# Schematic.net
KiCad netlist of a schematic drawn in EAGLE
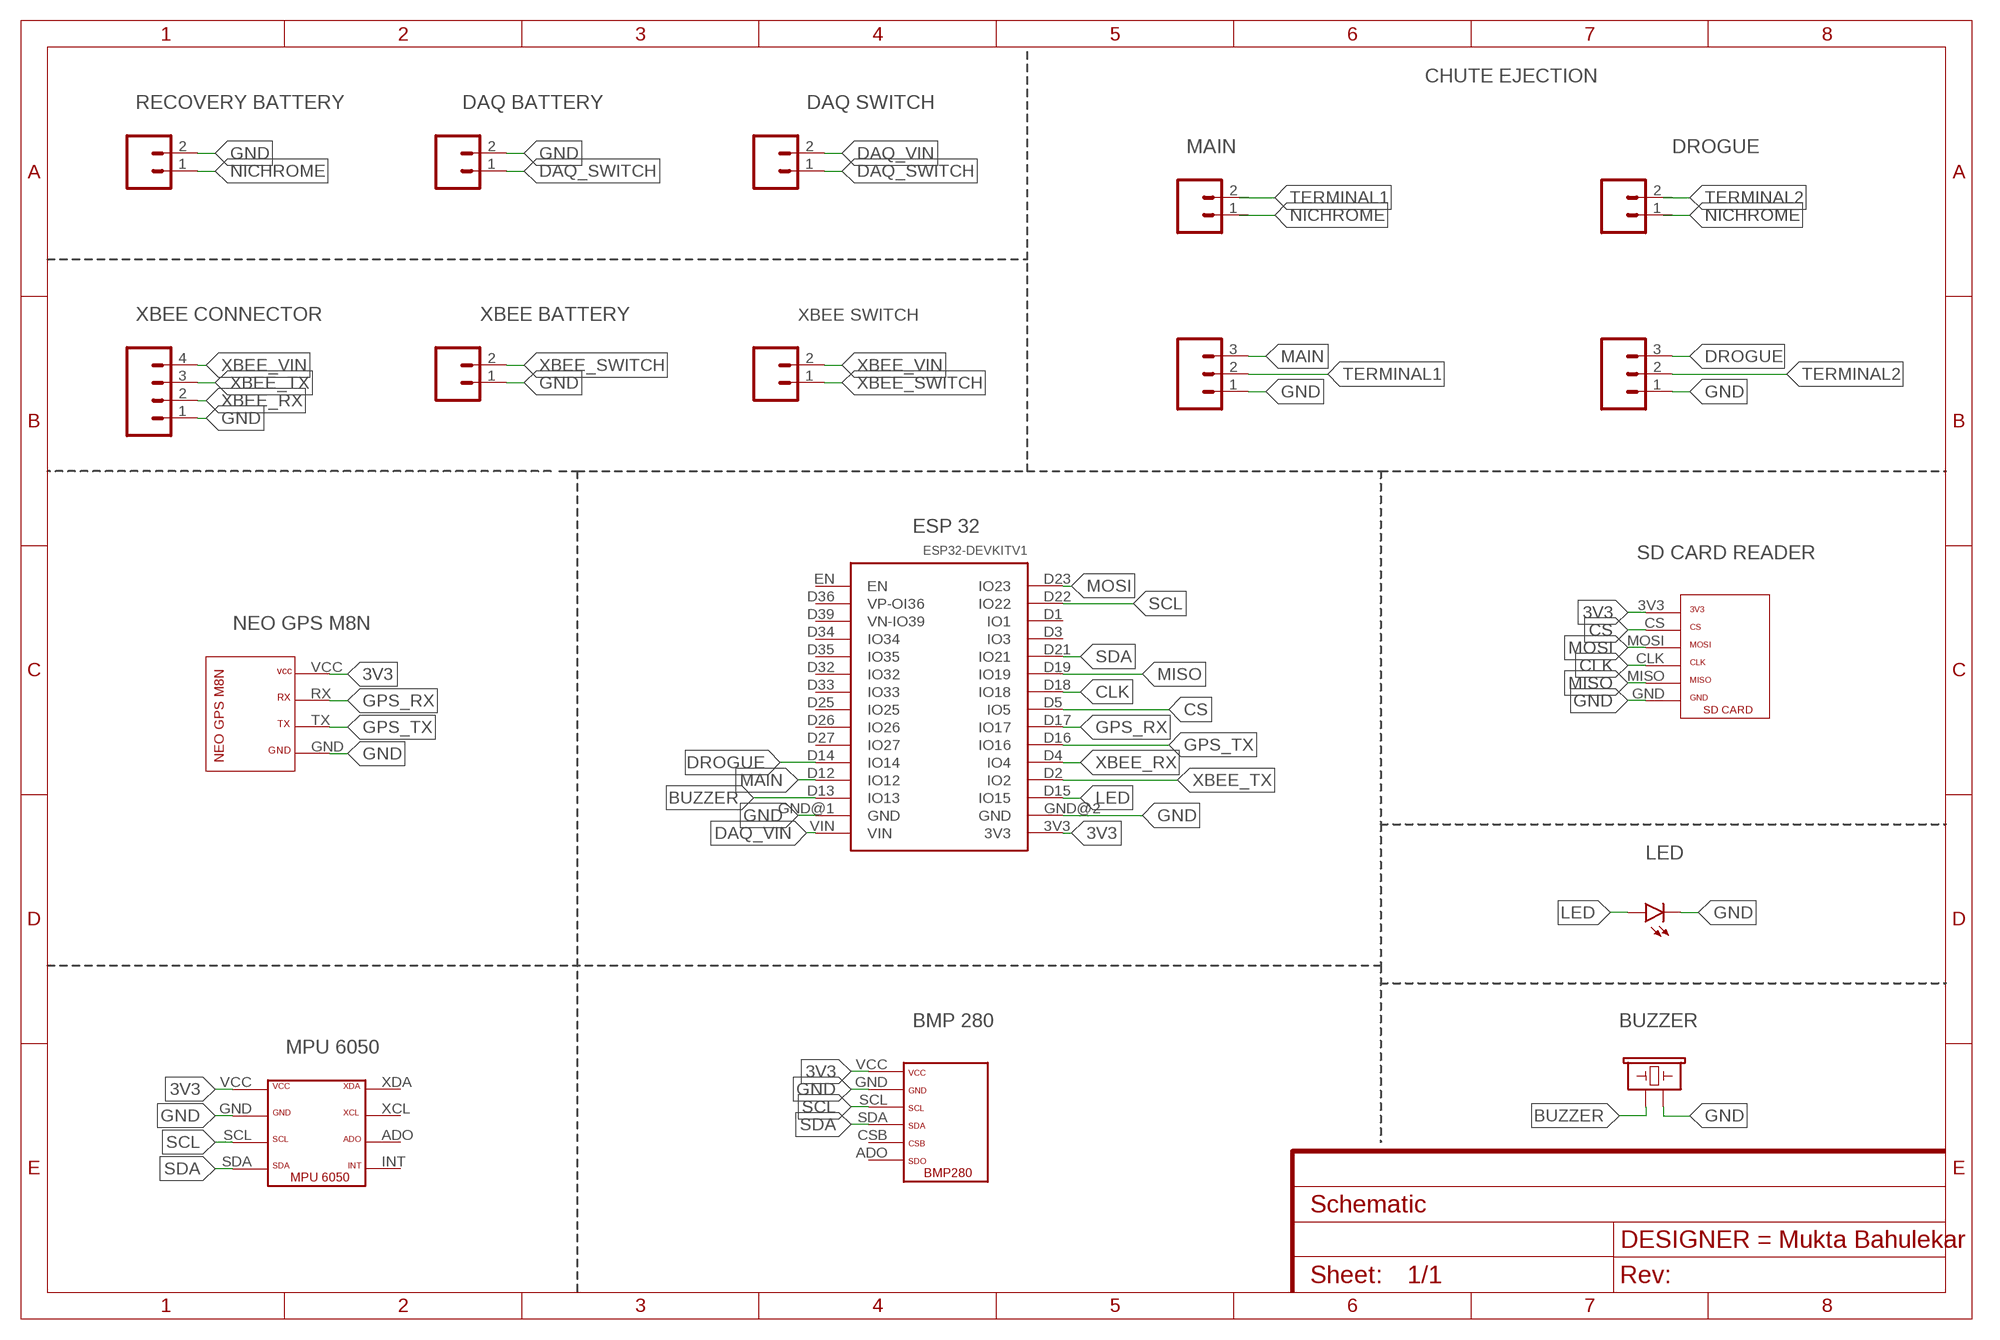
[diagram p0: schematic, sheet 1]

(export (version "E")
  (design (tool "Eeschema 10.0.6"))
  (components
    (comp (ref "J1")
      (value "455-1750-1-ND")
      (footprint "eagle-import:1X03")
      (libsource (lib "eagle-import") (part "CONN_03"))
    )
    (comp (ref "J2")
      (value "455-1750-1-ND")
      (footprint "eagle-import:1X03")
      (libsource (lib "eagle-import") (part "CONN_03"))
    )
    (comp (ref "J8")
      (value "CONN_02PTH4")
      (footprint "eagle-import:1X02_XTRA_BIG")
      (libsource (lib "eagle-import") (part "CONN_02PTH4"))
    )
    (comp (ref "J11")
      (value "CONN_04PTH")
      (footprint "eagle-import:1X04")
      (libsource (lib "eagle-import") (part "CONN_04PTH"))
    )
    (comp (ref "J12")
      (value "CONN_02PTH4")
      (footprint "eagle-import:1X02_XTRA_BIG")
      (libsource (lib "eagle-import") (part "CONN_02PTH4"))
    )
    (comp (ref "J13")
      (value "CONN_02PTH4")
      (footprint "eagle-import:1X02_XTRA_BIG")
      (libsource (lib "eagle-import") (part "CONN_02PTH4"))
    )
    (comp (ref "J14")
      (value "CONN_02PTH4")
      (footprint "eagle-import:1X02_XTRA_BIG")
      (libsource (lib "eagle-import") (part "CONN_02PTH4"))
    )
    (comp (ref "J15")
      (value "CONN_02PTH4")
      (footprint "eagle-import:1X02_XTRA_BIG")
      (libsource (lib "eagle-import") (part "CONN_02PTH4"))
    )
    (comp (ref "J16")
      (value "CONN_02PTH4")
      (footprint "eagle-import:1X02_XTRA_BIG")
      (libsource (lib "eagle-import") (part "CONN_02PTH4"))
    )
    (comp (ref "J17")
      (value "CONN_02PTH4")
      (footprint "eagle-import:1X02_XTRA_BIG")
      (libsource (lib "eagle-import") (part "CONN_02PTH4"))
    )
    (comp (ref "LED1")
      (value "LED5MM")
      (footprint "eagle-import:LED5MM")
      (libsource (lib "eagle-import") (part "LED5MM"))
    )
    (comp (ref "LS1")
      (value "BUZZER-PTH")
      (footprint "eagle-import:BUZZER-12MM")
      (libsource (lib "eagle-import") (part "BUZZER-PTH"))
    )
    (comp (ref "U$1")
      (value "ESP32DEVKITV1")
      (footprint "eagle-import:ESP32-DEVKITV1")
      (libsource (lib "eagle-import") (part "ESP32DEVKITV1"))
    )
    (comp (ref "U$2")
      (value "BMP280")
      (footprint "eagle-import:BMP280")
      (libsource (lib "eagle-import") (part "BMP280"))
    )
    (comp (ref "U$3")
      (value "MINISD")
      (footprint "eagle-import:MINISD")
      (libsource (lib "eagle-import") (part "MINISD"))
    )
    (comp (ref "U$4")
      (value "MPU6050")
      (footprint "eagle-import:MPU6050")
      (libsource (lib "eagle-import") (part "MPU6050"))
    )
    (comp (ref "U$5")
      (value "NEOM8N")
      (footprint "eagle-import:NEOM8M")
      (libsource (lib "eagle-import") (part "NEOM8N"))
    )
  )
  (nets
    (net (code "1") (name "3V3") (class "Default")
      (node (ref "U$1") (pin "3V3") (pinfunction "3V3_3V3") (pintype "bidirectional"))
      (node (ref "U$2") (pin "VCC") (pinfunction "VCC_VCC") (pintype "bidirectional"))
      (node (ref "U$3") (pin "3V3") (pinfunction "3V3_3V3") (pintype "bidirectional"))
      (node (ref "U$4") (pin "VCC") (pinfunction "VCC_VCC") (pintype "bidirectional"))
      (node (ref "U$5") (pin "VCC") (pinfunction "VCC_VCC") (pintype "bidirectional"))
    )
    (net (code "2") (name "BUZZER") (class "Default")
      (node (ref "LS1") (pin "+") (pinfunction "1_+") (pintype "passive"))
      (node (ref "U$1") (pin "D13") (pinfunction "IO13_D13") (pintype "bidirectional"))
    )
    (net (code "3") (name "CLK") (class "Default")
      (node (ref "U$1") (pin "D18") (pinfunction "IO18_D18") (pintype "bidirectional"))
      (node (ref "U$3") (pin "CLK") (pinfunction "CLK_CLK") (pintype "bidirectional"))
    )
    (net (code "4") (name "CS") (class "Default")
      (node (ref "U$1") (pin "D5") (pinfunction "IO5_D5") (pintype "bidirectional"))
      (node (ref "U$3") (pin "CS") (pinfunction "CS_CS") (pintype "bidirectional"))
    )
    (net (code "5") (name "DAQ_SWITCH") (class "Default")
      (node (ref "J12") (pin "1") (pinfunction "1_1") (pintype "passive"))
      (node (ref "J13") (pin "1") (pinfunction "1_1") (pintype "passive"))
    )
    (net (code "6") (name "DAQ_VIN") (class "Default")
      (node (ref "J13") (pin "2") (pinfunction "2_2") (pintype "passive"))
      (node (ref "U$1") (pin "VIN") (pinfunction "VIN_VIN") (pintype "bidirectional"))
    )
    (net (code "7") (name "DROGUE") (class "Default")
      (node (ref "J1") (pin "3") (pinfunction "3_3") (pintype "passive"))
      (node (ref "U$1") (pin "D14") (pinfunction "IO14_D14") (pintype "bidirectional"))
    )
    (net (code "8") (name "GND") (class "Default")
      (node (ref "J1") (pin "1") (pinfunction "1_1") (pintype "passive"))
      (node (ref "J11") (pin "1") (pinfunction "1_1") (pintype "passive"))
      (node (ref "J12") (pin "2") (pinfunction "2_2") (pintype "passive"))
      (node (ref "J15") (pin "1") (pinfunction "1_1") (pintype "passive"))
      (node (ref "J2") (pin "1") (pinfunction "1_1") (pintype "passive"))
      (node (ref "J8") (pin "2") (pinfunction "2_2") (pintype "passive"))
      (node (ref "LED1") (pin "K") (pinfunction "C_K") (pintype "passive"))
      (node (ref "LS1") (pin "-") (pinfunction "2_-") (pintype "passive"))
      (node (ref "U$1") (pin "GND@1") (pinfunction "GND_GND@1") (pintype "bidirectional"))
      (node (ref "U$1") (pin "GND@2") (pinfunction "GND_GND@2") (pintype "bidirectional"))
      (node (ref "U$2") (pin "GND") (pinfunction "GND_GND") (pintype "bidirectional"))
      (node (ref "U$3") (pin "GND") (pinfunction "GND_GND") (pintype "bidirectional"))
      (node (ref "U$4") (pin "GND") (pinfunction "GND_GND") (pintype "bidirectional"))
      (node (ref "U$5") (pin "GND") (pinfunction "GND_GND") (pintype "bidirectional"))
    )
    (net (code "9") (name "GPS_RX") (class "Default")
      (node (ref "U$1") (pin "D17") (pinfunction "IO17_D17") (pintype "bidirectional"))
      (node (ref "U$5") (pin "RX") (pinfunction "RX_RX") (pintype "bidirectional"))
    )
    (net (code "10") (name "GPS_TX") (class "Default")
      (node (ref "U$1") (pin "D16") (pinfunction "IO16_D16") (pintype "bidirectional"))
      (node (ref "U$5") (pin "TX") (pinfunction "TX_TX") (pintype "bidirectional"))
    )
    (net (code "11") (name "LED") (class "Default")
      (node (ref "LED1") (pin "A") (pinfunction "A_A") (pintype "passive"))
      (node (ref "U$1") (pin "D15") (pinfunction "IO15_D15") (pintype "bidirectional"))
    )
    (net (code "12") (name "MAIN") (class "Default")
      (node (ref "J2") (pin "3") (pinfunction "3_3") (pintype "passive"))
      (node (ref "U$1") (pin "D12") (pinfunction "IO12_D12") (pintype "bidirectional"))
    )
    (net (code "13") (name "MISO") (class "Default")
      (node (ref "U$1") (pin "D19") (pinfunction "IO19_D19") (pintype "bidirectional"))
      (node (ref "U$3") (pin "MISO") (pinfunction "MISO_MISO") (pintype "bidirectional"))
    )
    (net (code "14") (name "MOSI") (class "Default")
      (node (ref "U$1") (pin "D23") (pinfunction "IO23_D23") (pintype "bidirectional"))
      (node (ref "U$3") (pin "MOSI") (pinfunction "MOSI_MOSI") (pintype "bidirectional"))
    )
    (net (code "15") (name "NICHROME") (class "Default")
      (node (ref "J16") (pin "1") (pinfunction "1_1") (pintype "passive"))
      (node (ref "J17") (pin "1") (pinfunction "1_1") (pintype "passive"))
      (node (ref "J8") (pin "1") (pinfunction "1_1") (pintype "passive"))
    )
    (net (code "16") (name "SCL") (class "Default")
      (node (ref "U$1") (pin "D22") (pinfunction "IO22_D22") (pintype "bidirectional"))
      (node (ref "U$2") (pin "SCL") (pinfunction "SCL_SCL") (pintype "bidirectional"))
      (node (ref "U$4") (pin "SCL") (pinfunction "SCL_SCL") (pintype "bidirectional"))
    )
    (net (code "17") (name "SDA") (class "Default")
      (node (ref "U$1") (pin "D21") (pinfunction "IO21_D21") (pintype "bidirectional"))
      (node (ref "U$2") (pin "SDA") (pinfunction "SDA_SDA") (pintype "bidirectional"))
      (node (ref "U$4") (pin "SDA") (pinfunction "SDA_SDA") (pintype "bidirectional"))
    )
    (net (code "18") (name "TERMINAL1") (class "Default")
      (node (ref "J16") (pin "2") (pinfunction "2_2") (pintype "passive"))
      (node (ref "J2") (pin "2") (pinfunction "2_2") (pintype "passive"))
    )
    (net (code "19") (name "TERMINAL2") (class "Default")
      (node (ref "J1") (pin "2") (pinfunction "2_2") (pintype "passive"))
      (node (ref "J17") (pin "2") (pinfunction "2_2") (pintype "passive"))
    )
    (net (code "20") (name "XBEE_RX") (class "Default")
      (node (ref "J11") (pin "2") (pinfunction "2_2") (pintype "passive"))
      (node (ref "U$1") (pin "D4") (pinfunction "IO4_D4") (pintype "bidirectional"))
    )
    (net (code "21") (name "XBEE_SWITCH") (class "Default")
      (node (ref "J14") (pin "1") (pinfunction "1_1") (pintype "passive"))
      (node (ref "J15") (pin "2") (pinfunction "2_2") (pintype "passive"))
    )
    (net (code "22") (name "XBEE_TX") (class "Default")
      (node (ref "J11") (pin "3") (pinfunction "3_3") (pintype "passive"))
      (node (ref "U$1") (pin "D2") (pinfunction "IO2_D2") (pintype "bidirectional"))
    )
    (net (code "23") (name "XBEE_VIN") (class "Default")
      (node (ref "J11") (pin "4") (pinfunction "4_4") (pintype "passive"))
      (node (ref "J14") (pin "2") (pinfunction "2_2") (pintype "passive"))
    )
    (net (code "24") (name "unconnected-(U$1-IO1-PadD1)") (class "Default")
      (node (ref "U$1") (pin "D1") (pinfunction "IO1_D1") (pintype "bidirectional"))
    )
    (net (code "25") (name "unconnected-(U$1-IO3-PadD3)") (class "Default")
      (node (ref "U$1") (pin "D3") (pinfunction "IO3_D3") (pintype "bidirectional"))
    )
    (net (code "26") (name "unconnected-(U$1-IO25-PadD25)") (class "Default")
      (node (ref "U$1") (pin "D25") (pinfunction "IO25_D25") (pintype "bidirectional"))
    )
    (net (code "27") (name "unconnected-(U$1-IO26-PadD26)") (class "Default")
      (node (ref "U$1") (pin "D26") (pinfunction "IO26_D26") (pintype "bidirectional"))
    )
    (net (code "28") (name "unconnected-(U$1-IO27-PadD27)") (class "Default")
      (node (ref "U$1") (pin "D27") (pinfunction "IO27_D27") (pintype "bidirectional"))
    )
    (net (code "29") (name "unconnected-(U$1-IO32-PadD32)") (class "Default")
      (node (ref "U$1") (pin "D32") (pinfunction "IO32_D32") (pintype "bidirectional"))
    )
    (net (code "30") (name "unconnected-(U$1-IO33-PadD33)") (class "Default")
      (node (ref "U$1") (pin "D33") (pinfunction "IO33_D33") (pintype "bidirectional"))
    )
    (net (code "31") (name "unconnected-(U$1-IO34-PadD34)") (class "Default")
      (node (ref "U$1") (pin "D34") (pinfunction "IO34_D34") (pintype "bidirectional"))
    )
    (net (code "32") (name "unconnected-(U$1-IO35-PadD35)") (class "Default")
      (node (ref "U$1") (pin "D35") (pinfunction "IO35_D35") (pintype "bidirectional"))
    )
    (net (code "33") (name "unconnected-(U$1-PadEN)") (class "Default")
      (node (ref "U$1") (pin "EN") (pinfunction "EN_EN") (pintype "bidirectional"))
    )
    (net (code "34") (name "unconnected-(U$1-VN-IO39-PadD39)") (class "Default")
      (node (ref "U$1") (pin "D39") (pinfunction "VN-IO39_D39") (pintype "bidirectional"))
    )
    (net (code "35") (name "unconnected-(U$1-VP-OI36-PadD36)") (class "Default")
      (node (ref "U$1") (pin "D36") (pinfunction "VP-OI36_D36") (pintype "bidirectional"))
    )
    (net (code "36") (name "unconnected-(U$2-PadCSB)") (class "Default")
      (node (ref "U$2") (pin "CSB") (pinfunction "CSB_CSB") (pintype "bidirectional"))
    )
    (net (code "37") (name "unconnected-(U$2-SDO-PadADO)") (class "Default")
      (node (ref "U$2") (pin "ADO") (pinfunction "SDO_ADO") (pintype "bidirectional"))
    )
    (net (code "38") (name "unconnected-(U$4-PadADO)") (class "Default")
      (node (ref "U$4") (pin "ADO") (pinfunction "ADO_ADO") (pintype "bidirectional"))
    )
    (net (code "39") (name "unconnected-(U$4-PadINT)") (class "Default")
      (node (ref "U$4") (pin "INT") (pinfunction "INT_INT") (pintype "bidirectional"))
    )
    (net (code "40") (name "unconnected-(U$4-PadXCL)") (class "Default")
      (node (ref "U$4") (pin "XCL") (pinfunction "XCL_XCL") (pintype "bidirectional"))
    )
    (net (code "41") (name "unconnected-(U$4-PadXDA)") (class "Default")
      (node (ref "U$4") (pin "XDA") (pinfunction "XDA_XDA") (pintype "bidirectional"))
    )
  )
)
